# schematic.net
KiCad netlist of a schematic drawn in EAGLE
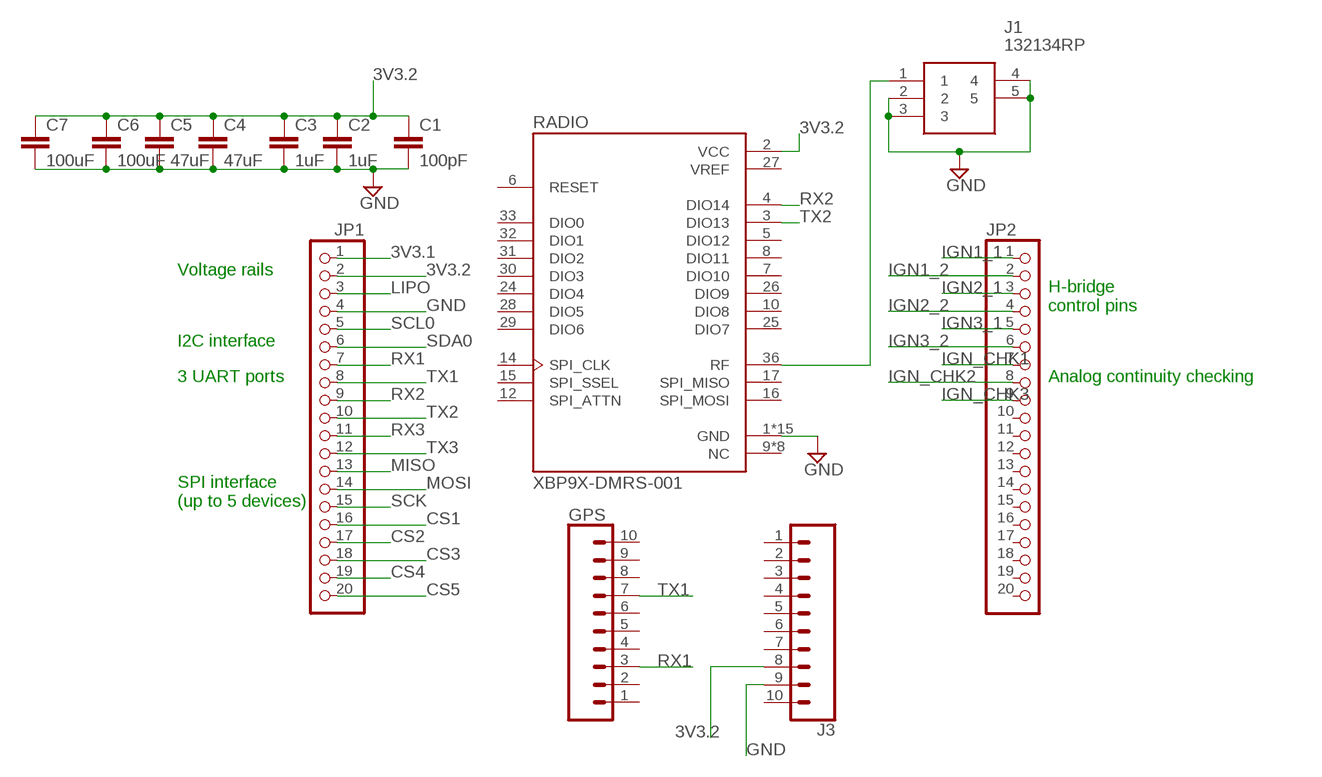
[diagram p0: schematic, sheet 1]

(export (version "E")
  (design (tool "Eeschema 10.0.6"))
  (components
    (comp (ref "C1")
      (value "100pF")
      (footprint "eagle-import:0603")
      (libsource (lib "eagle-import") (part "0.1UF-0603-100V-10%"))
    )
    (comp (ref "C2")
      (value "1uF")
      (footprint "eagle-import:1206")
      (libsource (lib "eagle-import") (part "2.2UF-CERCAP-10009"))
    )
    (comp (ref "C3")
      (value "1uF")
      (footprint "eagle-import:1206")
      (libsource (lib "eagle-import") (part "2.2UF-CERCAP-10009"))
    )
    (comp (ref "C4")
      (value "47uF")
      (footprint "eagle-import:1206")
      (libsource (lib "eagle-import") (part "2.2UF-CERCAP-10009"))
    )
    (comp (ref "C5")
      (value "47uF")
      (footprint "eagle-import:1206")
      (libsource (lib "eagle-import") (part "2.2UF-CERCAP-10009"))
    )
    (comp (ref "C6")
      (value "100uF")
      (footprint "eagle-import:1206")
      (libsource (lib "eagle-import") (part "2.2UF-CERCAP-10009"))
    )
    (comp (ref "C7")
      (value "100uF")
      (footprint "eagle-import:1206")
      (libsource (lib "eagle-import") (part "2.2UF-CERCAP-10009"))
    )
    (comp (ref "GPS")
      (value "CONN_10NO_SILK_PTH_FEMALE")
      (footprint "eagle-import:1X10_NO_SILK")
      (libsource (lib "eagle-import") (part "CONN_10NO_SILK_PTH_FEMALE"))
    )
    (comp (ref "J1")
      (value "132134RP")
      (footprint "eagle-import:132134RP")
      (fields (field (name "MOUSER_PART_NUMBER") "523-132134RP"))
      (libsource (lib "eagle-import") (part "132134RP"))
    )
    (comp (ref "J3")
      (value "CONN_10NO_SILK_PTH_FEMALE")
      (footprint "eagle-import:1X10_NO_SILK")
      (libsource (lib "eagle-import") (part "CONN_10NO_SILK_PTH_FEMALE"))
    )
    (comp (ref "JP1")
      (value "PINHD-1X20")
      (footprint "eagle-import:1X20")
      (libsource (lib "eagle-import") (part "PINHD-1X20"))
    )
    (comp (ref "JP2")
      (value "PINHD-1X20")
      (footprint "eagle-import:1X20")
      (libsource (lib "eagle-import") (part "PINHD-1X20"))
    )
    (comp (ref "RADIO")
      (value "XBP9X-DMRS-001")
      (footprint "eagle-import:MODULE_XBP9X-DMRS-001")
      (fields (field (name "MF") "Digi International"))
      (libsource (lib "eagle-import") (part "XBP9X-DMRS-001"))
    )
  )
  (nets
    (net (code "1") (name "/3V3.1") (class "Default")
      (node (ref "JP1") (pin "1") (pinfunction "1_1") (pintype "passive"))
    )
    (net (code "2") (name "/3V3.2") (class "Default")
      (node (ref "C1") (pin "1") (pinfunction "1_1") (pintype "passive"))
      (node (ref "C2") (pin "1") (pinfunction "1_1") (pintype "passive"))
      (node (ref "C3") (pin "1") (pinfunction "1_1") (pintype "passive"))
      (node (ref "C4") (pin "1") (pinfunction "1_1") (pintype "passive"))
      (node (ref "C5") (pin "1") (pinfunction "1_1") (pintype "passive"))
      (node (ref "C6") (pin "1") (pinfunction "1_1") (pintype "passive"))
      (node (ref "C7") (pin "1") (pinfunction "1_1") (pintype "passive"))
      (node (ref "J3") (pin "8") (pinfunction "8_8") (pintype "passive"))
      (node (ref "JP1") (pin "2") (pinfunction "2_2") (pintype "passive"))
      (node (ref "RADIO") (pin "2") (pinfunction "VCC_2") (pintype "power_in"))
    )
    (net (code "3") (name "/CS1") (class "Default")
      (node (ref "JP1") (pin "16") (pinfunction "16_16") (pintype "passive"))
    )
    (net (code "4") (name "/CS2") (class "Default")
      (node (ref "JP1") (pin "17") (pinfunction "17_17") (pintype "passive"))
    )
    (net (code "5") (name "/CS3") (class "Default")
      (node (ref "JP1") (pin "18") (pinfunction "18_18") (pintype "passive"))
    )
    (net (code "6") (name "/CS4") (class "Default")
      (node (ref "JP1") (pin "19") (pinfunction "19_19") (pintype "passive"))
    )
    (net (code "7") (name "/CS5") (class "Default")
      (node (ref "JP1") (pin "20") (pinfunction "20_20") (pintype "passive"))
    )
    (net (code "8") (name "/IGN1_1") (class "Default")
      (node (ref "JP2") (pin "1") (pinfunction "1_1") (pintype "passive"))
    )
    (net (code "9") (name "/IGN1_2") (class "Default")
      (node (ref "JP2") (pin "2") (pinfunction "2_2") (pintype "passive"))
    )
    (net (code "10") (name "/IGN2_1") (class "Default")
      (node (ref "JP2") (pin "3") (pinfunction "3_3") (pintype "passive"))
    )
    (net (code "11") (name "/IGN2_2") (class "Default")
      (node (ref "JP2") (pin "4") (pinfunction "4_4") (pintype "passive"))
    )
    (net (code "12") (name "/IGN3_1") (class "Default")
      (node (ref "JP2") (pin "5") (pinfunction "5_5") (pintype "passive"))
    )
    (net (code "13") (name "/IGN3_2") (class "Default")
      (node (ref "JP2") (pin "6") (pinfunction "6_6") (pintype "passive"))
    )
    (net (code "14") (name "/IGN_CHK1") (class "Default")
      (node (ref "JP2") (pin "7") (pinfunction "7_7") (pintype "passive"))
    )
    (net (code "15") (name "/IGN_CHK2") (class "Default")
      (node (ref "JP2") (pin "8") (pinfunction "8_8") (pintype "passive"))
    )
    (net (code "16") (name "/IGN_CHK3") (class "Default")
      (node (ref "JP2") (pin "9") (pinfunction "9_9") (pintype "passive"))
    )
    (net (code "17") (name "/LIPO") (class "Default")
      (node (ref "JP1") (pin "3") (pinfunction "3_3") (pintype "passive"))
    )
    (net (code "18") (name "/MISO") (class "Default")
      (node (ref "JP1") (pin "13") (pinfunction "13_13") (pintype "passive"))
    )
    (net (code "19") (name "/MOSI") (class "Default")
      (node (ref "JP1") (pin "14") (pinfunction "14_14") (pintype "passive"))
    )
    (net (code "20") (name "/RX1") (class "Default")
      (node (ref "GPS") (pin "3") (pinfunction "3_3") (pintype "passive"))
      (node (ref "JP1") (pin "7") (pinfunction "7_7") (pintype "passive"))
    )
    (net (code "21") (name "/RX2") (class "Default")
      (node (ref "JP1") (pin "9") (pinfunction "9_9") (pintype "passive"))
      (node (ref "RADIO") (pin "4") (pinfunction "DIO14_4") (pintype "bidirectional"))
    )
    (net (code "22") (name "/RX3") (class "Default")
      (node (ref "JP1") (pin "11") (pinfunction "11_11") (pintype "passive"))
    )
    (net (code "23") (name "/SCK") (class "Default")
      (node (ref "JP1") (pin "15") (pinfunction "15_15") (pintype "passive"))
    )
    (net (code "24") (name "/SCL0") (class "Default")
      (node (ref "JP1") (pin "5") (pinfunction "5_5") (pintype "passive"))
    )
    (net (code "25") (name "/SDA0") (class "Default")
      (node (ref "JP1") (pin "6") (pinfunction "6_6") (pintype "passive"))
    )
    (net (code "26") (name "/TX1") (class "Default")
      (node (ref "GPS") (pin "7") (pinfunction "7_7") (pintype "passive"))
      (node (ref "JP1") (pin "8") (pinfunction "8_8") (pintype "passive"))
    )
    (net (code "27") (name "/TX2") (class "Default")
      (node (ref "JP1") (pin "10") (pinfunction "10_10") (pintype "passive"))
      (node (ref "RADIO") (pin "3") (pinfunction "DIO13_3") (pintype "bidirectional"))
    )
    (net (code "28") (name "/TX3") (class "Default")
      (node (ref "JP1") (pin "12") (pinfunction "12_12") (pintype "passive"))
    )
    (net (code "29") (name "/VREF") (class "Default")
      (node (ref "RADIO") (pin "27") (pinfunction "VREF_27") (pintype "power_in"))
    )
    (net (code "30") (name "GND") (class "Default")
      (node (ref "C1") (pin "2") (pinfunction "2_2") (pintype "passive"))
      (node (ref "C2") (pin "2") (pinfunction "2_2") (pintype "passive"))
      (node (ref "C3") (pin "2") (pinfunction "2_2") (pintype "passive"))
      (node (ref "C4") (pin "2") (pinfunction "2_2") (pintype "passive"))
      (node (ref "C5") (pin "2") (pinfunction "2_2") (pintype "passive"))
      (node (ref "C6") (pin "2") (pinfunction "2_2") (pintype "passive"))
      (node (ref "C7") (pin "2") (pinfunction "2_2") (pintype "passive"))
      (node (ref "J1") (pin "2") (pinfunction "2_2") (pintype "bidirectional"))
      (node (ref "J1") (pin "3") (pinfunction "3_3") (pintype "bidirectional"))
      (node (ref "J1") (pin "4") (pinfunction "4_4") (pintype "bidirectional"))
      (node (ref "J1") (pin "5") (pinfunction "5_5") (pintype "bidirectional"))
      (node (ref "J3") (pin "9") (pinfunction "9_9") (pintype "passive"))
      (node (ref "JP1") (pin "4") (pinfunction "4_4") (pintype "passive"))
      (node (ref "RADIO") (pin "1") (pinfunction "GND_1") (pintype "power_in"))
      (node (ref "RADIO") (pin "11") (pinfunction "GND_11") (pintype "power_in"))
      (node (ref "RADIO") (pin "13") (pinfunction "GND_13") (pintype "power_in"))
      (node (ref "RADIO") (pin "22") (pinfunction "GND_22") (pintype "power_in"))
      (node (ref "RADIO") (pin "35") (pinfunction "GND_35") (pintype "power_in"))
      (node (ref "RADIO") (pin "38") (pinfunction "GND_38") (pintype "power_in"))
      (node (ref "RADIO") (pin "V38_1") (pinfunction "GND_V38_1") (pintype "power_in"))
      (node (ref "RADIO") (pin "V38_2") (pinfunction "GND_V38_2") (pintype "power_in"))
      (node (ref "RADIO") (pin "V38_3") (pinfunction "GND_V38_3") (pintype "power_in"))
      (node (ref "RADIO") (pin "V38_4") (pinfunction "GND_V38_4") (pintype "power_in"))
      (node (ref "RADIO") (pin "V38_5") (pinfunction "GND_V38_5") (pintype "power_in"))
      (node (ref "RADIO") (pin "V38_6") (pinfunction "GND_V38_6") (pintype "power_in"))
      (node (ref "RADIO") (pin "V38_7") (pinfunction "GND_V38_7") (pintype "power_in"))
      (node (ref "RADIO") (pin "V38_8") (pinfunction "GND_V38_8") (pintype "power_in"))
      (node (ref "RADIO") (pin "V38_9") (pinfunction "GND_V38_9") (pintype "power_in"))
    )
    (net (code "31") (name "Net-(RADIO-RF)") (class "Default")
      (node (ref "J1") (pin "1") (pinfunction "1_1") (pintype "bidirectional"))
      (node (ref "RADIO") (pin "36") (pinfunction "RF_36") (pintype "bidirectional"))
    )
    (net (code "32") (name "unconnected-(GPS-Pad1)") (class "Default")
      (node (ref "GPS") (pin "1") (pinfunction "1_1") (pintype "passive"))
    )
    (net (code "33") (name "unconnected-(GPS-Pad2)") (class "Default")
      (node (ref "GPS") (pin "2") (pinfunction "2_2") (pintype "passive"))
    )
    (net (code "34") (name "unconnected-(GPS-Pad4)") (class "Default")
      (node (ref "GPS") (pin "4") (pinfunction "4_4") (pintype "passive"))
    )
    (net (code "35") (name "unconnected-(GPS-Pad5)") (class "Default")
      (node (ref "GPS") (pin "5") (pinfunction "5_5") (pintype "passive"))
    )
    (net (code "36") (name "unconnected-(GPS-Pad6)") (class "Default")
      (node (ref "GPS") (pin "6") (pinfunction "6_6") (pintype "passive"))
    )
    (net (code "37") (name "unconnected-(GPS-Pad8)") (class "Default")
      (node (ref "GPS") (pin "8") (pinfunction "8_8") (pintype "passive"))
    )
    (net (code "38") (name "unconnected-(GPS-Pad9)") (class "Default")
      (node (ref "GPS") (pin "9") (pinfunction "9_9") (pintype "passive"))
    )
    (net (code "39") (name "unconnected-(GPS-Pad10)") (class "Default")
      (node (ref "GPS") (pin "10") (pinfunction "10_10") (pintype "passive"))
    )
    (net (code "40") (name "unconnected-(J3-Pad1)") (class "Default")
      (node (ref "J3") (pin "1") (pinfunction "1_1") (pintype "passive"))
    )
    (net (code "41") (name "unconnected-(J3-Pad2)") (class "Default")
      (node (ref "J3") (pin "2") (pinfunction "2_2") (pintype "passive"))
    )
    (net (code "42") (name "unconnected-(J3-Pad3)") (class "Default")
      (node (ref "J3") (pin "3") (pinfunction "3_3") (pintype "passive"))
    )
    (net (code "43") (name "unconnected-(J3-Pad4)") (class "Default")
      (node (ref "J3") (pin "4") (pinfunction "4_4") (pintype "passive"))
    )
    (net (code "44") (name "unconnected-(J3-Pad5)") (class "Default")
      (node (ref "J3") (pin "5") (pinfunction "5_5") (pintype "passive"))
    )
    (net (code "45") (name "unconnected-(J3-Pad6)") (class "Default")
      (node (ref "J3") (pin "6") (pinfunction "6_6") (pintype "passive"))
    )
    (net (code "46") (name "unconnected-(J3-Pad7)") (class "Default")
      (node (ref "J3") (pin "7") (pinfunction "7_7") (pintype "passive"))
    )
    (net (code "47") (name "unconnected-(J3-Pad10)") (class "Default")
      (node (ref "J3") (pin "10") (pinfunction "10_10") (pintype "passive"))
    )
    (net (code "48") (name "unconnected-(JP2-Pad10)") (class "Default")
      (node (ref "JP2") (pin "10") (pinfunction "10_10") (pintype "passive"))
    )
    (net (code "49") (name "unconnected-(JP2-Pad11)") (class "Default")
      (node (ref "JP2") (pin "11") (pinfunction "11_11") (pintype "passive"))
    )
    (net (code "50") (name "unconnected-(JP2-Pad12)") (class "Default")
      (node (ref "JP2") (pin "12") (pinfunction "12_12") (pintype "passive"))
    )
    (net (code "51") (name "unconnected-(JP2-Pad13)") (class "Default")
      (node (ref "JP2") (pin "13") (pinfunction "13_13") (pintype "passive"))
    )
    (net (code "52") (name "unconnected-(JP2-Pad14)") (class "Default")
      (node (ref "JP2") (pin "14") (pinfunction "14_14") (pintype "passive"))
    )
    (net (code "53") (name "unconnected-(JP2-Pad15)") (class "Default")
      (node (ref "JP2") (pin "15") (pinfunction "15_15") (pintype "passive"))
    )
    (net (code "54") (name "unconnected-(JP2-Pad16)") (class "Default")
      (node (ref "JP2") (pin "16") (pinfunction "16_16") (pintype "passive"))
    )
    (net (code "55") (name "unconnected-(JP2-Pad17)") (class "Default")
      (node (ref "JP2") (pin "17") (pinfunction "17_17") (pintype "passive"))
    )
    (net (code "56") (name "unconnected-(JP2-Pad18)") (class "Default")
      (node (ref "JP2") (pin "18") (pinfunction "18_18") (pintype "passive"))
    )
    (net (code "57") (name "unconnected-(JP2-Pad19)") (class "Default")
      (node (ref "JP2") (pin "19") (pinfunction "19_19") (pintype "passive"))
    )
    (net (code "58") (name "unconnected-(JP2-Pad20)") (class "Default")
      (node (ref "JP2") (pin "20") (pinfunction "20_20") (pintype "passive"))
    )
    (net (code "59") (name "unconnected-(RADIO-DIO0-Pad33)") (class "Default")
      (node (ref "RADIO") (pin "33") (pinfunction "DIO0_33") (pintype "bidirectional"))
    )
    (net (code "60") (name "unconnected-(RADIO-DIO1-Pad32)") (class "Default")
      (node (ref "RADIO") (pin "32") (pinfunction "DIO1_32") (pintype "bidirectional"))
    )
    (net (code "61") (name "unconnected-(RADIO-DIO2-Pad31)") (class "Default")
      (node (ref "RADIO") (pin "31") (pinfunction "DIO2_31") (pintype "bidirectional"))
    )
    (net (code "62") (name "unconnected-(RADIO-DIO3-Pad30)") (class "Default")
      (node (ref "RADIO") (pin "30") (pinfunction "DIO3_30") (pintype "bidirectional"))
    )
    (net (code "63") (name "unconnected-(RADIO-DIO4-Pad24)") (class "Default")
      (node (ref "RADIO") (pin "24") (pinfunction "DIO4_24") (pintype "bidirectional"))
    )
    (net (code "64") (name "unconnected-(RADIO-DIO5-Pad28)") (class "Default")
      (node (ref "RADIO") (pin "28") (pinfunction "DIO5_28") (pintype "bidirectional"))
    )
    (net (code "65") (name "unconnected-(RADIO-DIO6-Pad29)") (class "Default")
      (node (ref "RADIO") (pin "29") (pinfunction "DIO6_29") (pintype "bidirectional"))
    )
    (net (code "66") (name "unconnected-(RADIO-DIO7-Pad25)") (class "Default")
      (node (ref "RADIO") (pin "25") (pinfunction "DIO7_25") (pintype "bidirectional"))
    )
    (net (code "67") (name "unconnected-(RADIO-DIO8-Pad10)") (class "Default")
      (node (ref "RADIO") (pin "10") (pinfunction "DIO8_10") (pintype "bidirectional"))
    )
    (net (code "68") (name "unconnected-(RADIO-DIO9-Pad26)") (class "Default")
      (node (ref "RADIO") (pin "26") (pinfunction "DIO9_26") (pintype "bidirectional"))
    )
    (net (code "69") (name "unconnected-(RADIO-DIO10-Pad7)") (class "Default")
      (node (ref "RADIO") (pin "7") (pinfunction "DIO10_7") (pintype "bidirectional"))
    )
    (net (code "70") (name "unconnected-(RADIO-DIO11-Pad8)") (class "Default")
      (node (ref "RADIO") (pin "8") (pinfunction "DIO11_8") (pintype "bidirectional"))
    )
    (net (code "71") (name "unconnected-(RADIO-DIO12-Pad5)") (class "Default")
      (node (ref "RADIO") (pin "5") (pinfunction "DIO12_5") (pintype "bidirectional"))
    )
    (net (code "72") (name "unconnected-(RADIO-NC-Pad9)") (class "Default")
      (node (ref "RADIO") (pin "9") (pinfunction "NC_9") (pintype "no_connect"))
    )
    (net (code "73") (name "unconnected-(RADIO-NC-Pad18)") (class "Default")
      (node (ref "RADIO") (pin "18") (pinfunction "NC_18") (pintype "no_connect"))
    )
    (net (code "74") (name "unconnected-(RADIO-NC-Pad19)") (class "Default")
      (node (ref "RADIO") (pin "19") (pinfunction "NC_19") (pintype "no_connect"))
    )
    (net (code "75") (name "unconnected-(RADIO-NC-Pad20)") (class "Default")
      (node (ref "RADIO") (pin "20") (pinfunction "NC_20") (pintype "no_connect"))
    )
    (net (code "76") (name "unconnected-(RADIO-NC-Pad21)") (class "Default")
      (node (ref "RADIO") (pin "21") (pinfunction "NC_21") (pintype "no_connect"))
    )
    (net (code "77") (name "unconnected-(RADIO-NC-Pad23)") (class "Default")
      (node (ref "RADIO") (pin "23") (pinfunction "NC_23") (pintype "no_connect"))
    )
    (net (code "78") (name "unconnected-(RADIO-NC-Pad34)") (class "Default")
      (node (ref "RADIO") (pin "34") (pinfunction "NC_34") (pintype "no_connect"))
    )
    (net (code "79") (name "unconnected-(RADIO-NC-Pad37)") (class "Default")
      (node (ref "RADIO") (pin "37") (pinfunction "NC_37") (pintype "no_connect"))
    )
    (net (code "80") (name "unconnected-(RADIO-RESET-Pad6)") (class "Default")
      (node (ref "RADIO") (pin "6") (pinfunction "RESET_6") (pintype "bidirectional"))
    )
    (net (code "81") (name "unconnected-(RADIO-SPI_ATTN-Pad12)") (class "Default")
      (node (ref "RADIO") (pin "12") (pinfunction "SPI_ATTN_12") (pintype "bidirectional"))
    )
    (net (code "82") (name "unconnected-(RADIO-SPI_CLK-Pad14)") (class "Default")
      (node (ref "RADIO") (pin "14") (pinfunction "SPI_CLK_14") (pintype "bidirectional"))
    )
    (net (code "83") (name "unconnected-(RADIO-SPI_MISO-Pad17)") (class "Default")
      (node (ref "RADIO") (pin "17") (pinfunction "SPI_MISO_17") (pintype "bidirectional"))
    )
    (net (code "84") (name "unconnected-(RADIO-SPI_MOSI-Pad16)") (class "Default")
      (node (ref "RADIO") (pin "16") (pinfunction "SPI_MOSI_16") (pintype "bidirectional"))
    )
    (net (code "85") (name "unconnected-(RADIO-SPI_SSEL-Pad15)") (class "Default")
      (node (ref "RADIO") (pin "15") (pinfunction "SPI_SSEL_15") (pintype "bidirectional"))
    )
  )
)
